# Receiver.net
KiCad netlist of a schematic drawn in EAGLE
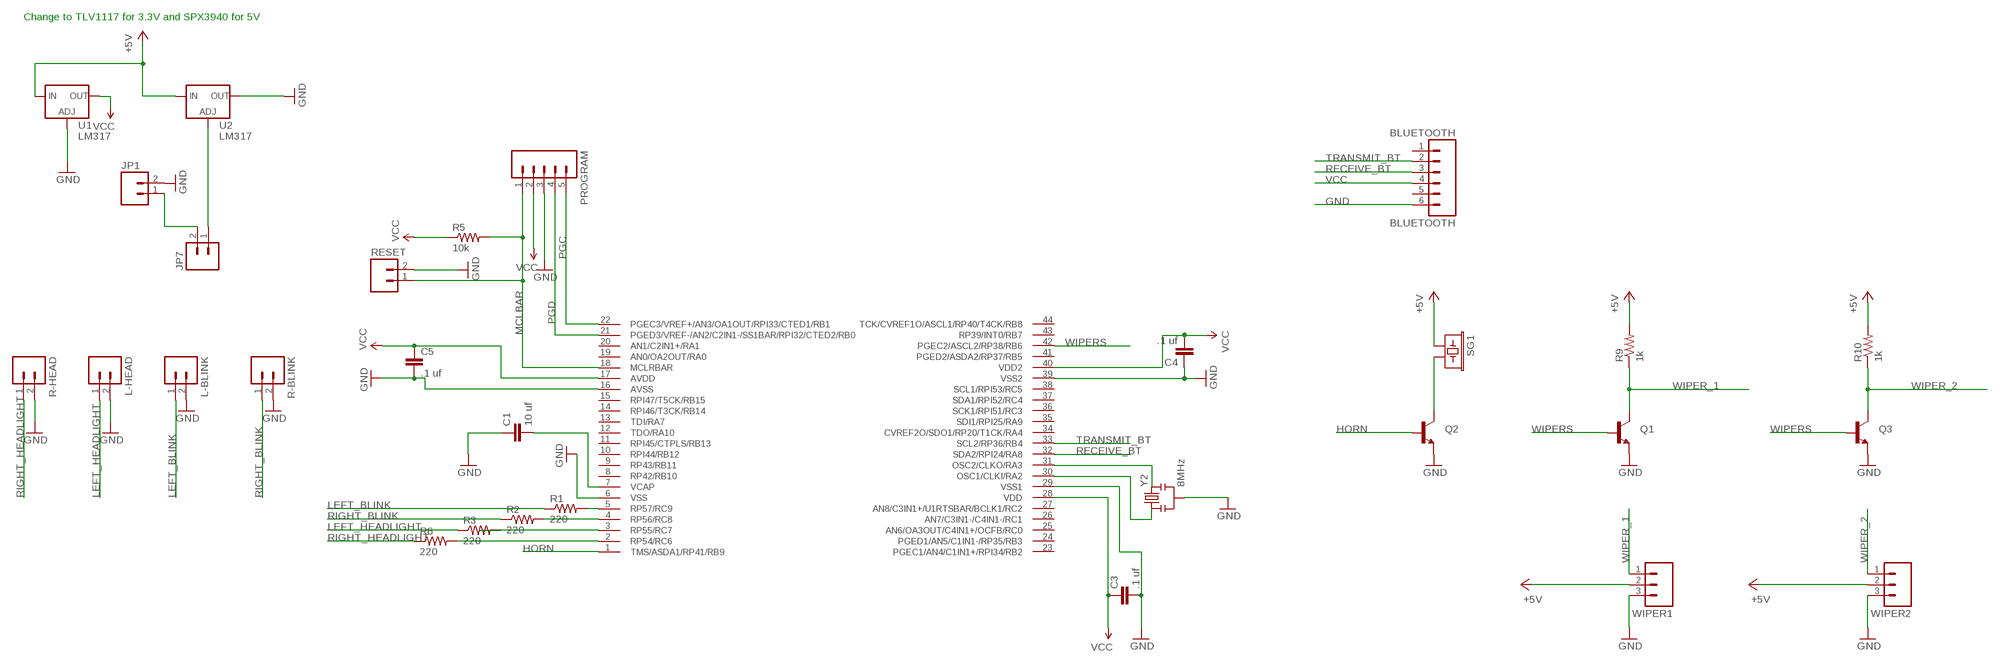
[diagram p0: schematic, sheet 1]

(export (version "E")
  (design (tool "Eeschema 10.0.6"))
  (components
    (comp (ref "BLUETOOTH")
      (value "BLUETOOTH")
      (footprint "eagle-import:MOLEX-1X6")
      (libsource (lib "eagle-import") (part "M06POLAR"))
    )
    (comp (ref "C1")
      (value "10 uf")
      (footprint "eagle-import:0603-CAP")
      (libsource (lib "eagle-import") (part "CAP0603-CAP"))
    )
    (comp (ref "C3")
      (value ".1 uf")
      (footprint "eagle-import:0603-CAP")
      (libsource (lib "eagle-import") (part "CAP0603-CAP"))
    )
    (comp (ref "C4")
      (value ".1 uf")
      (footprint "eagle-import:0603-CAP")
      (libsource (lib "eagle-import") (part "CAP0603-CAP"))
    )
    (comp (ref "C5")
      (value ".1 uf")
      (footprint "eagle-import:0603-CAP")
      (libsource (lib "eagle-import") (part "CAP0603-CAP"))
    )
    (comp (ref "JP1")
      (value "M02LOCK")
      (footprint "eagle-import:1X02_LOCK")
      (libsource (lib "eagle-import") (part "M02LOCK"))
    )
    (comp (ref "JP7")
      (value "M02LOCK")
      (footprint "eagle-import:1X02_LOCK")
      (libsource (lib "eagle-import") (part "M02LOCK"))
    )
    (comp (ref "L-BLINK")
      (value "M02LOCK")
      (footprint "eagle-import:1X02_LOCK")
      (libsource (lib "eagle-import") (part "M02LOCK"))
    )
    (comp (ref "L-HEAD")
      (value "M02LOCK")
      (footprint "eagle-import:1X02_LOCK")
      (libsource (lib "eagle-import") (part "M02LOCK"))
    )
    (comp (ref "PROGRAM")
      (value "M05LOCK")
      (footprint "eagle-import:1X05_LOCK")
      (libsource (lib "eagle-import") (part "M05LOCK"))
    )
    (comp (ref "Q1")
      (value "TRANSISTOR_NPNSOT23-3")
      (footprint "eagle-import:SOT23-3")
      (libsource (lib "eagle-import") (part "TRANSISTOR_NPNSOT23-3"))
    )
    (comp (ref "Q2")
      (value "TRANSISTOR_NPNSOT23-3")
      (footprint "eagle-import:SOT23-3")
      (libsource (lib "eagle-import") (part "TRANSISTOR_NPNSOT23-3"))
    )
    (comp (ref "Q3")
      (value "TRANSISTOR_NPNSOT23-3")
      (footprint "eagle-import:SOT23-3")
      (libsource (lib "eagle-import") (part "TRANSISTOR_NPNSOT23-3"))
    )
    (comp (ref "R-BLINK")
      (value "M02LOCK")
      (footprint "eagle-import:1X02_LOCK")
      (libsource (lib "eagle-import") (part "M02LOCK"))
    )
    (comp (ref "R-HEAD")
      (value "M02LOCK")
      (footprint "eagle-import:1X02_LOCK")
      (libsource (lib "eagle-import") (part "M02LOCK"))
    )
    (comp (ref "R1")
      (value "220")
      (footprint "eagle-import:0603-RES")
      (libsource (lib "eagle-import") (part "RESISTOR0603-RES"))
    )
    (comp (ref "R2")
      (value "220")
      (footprint "eagle-import:0603-RES")
      (libsource (lib "eagle-import") (part "RESISTOR0603-RES"))
    )
    (comp (ref "R3")
      (value "220")
      (footprint "eagle-import:0603-RES")
      (libsource (lib "eagle-import") (part "RESISTOR0603-RES"))
    )
    (comp (ref "R5")
      (value "10k")
      (footprint "eagle-import:0603-RES")
      (libsource (lib "eagle-import") (part "RESISTOR0603-RES"))
    )
    (comp (ref "R6")
      (value "220")
      (footprint "eagle-import:0603-RES")
      (libsource (lib "eagle-import") (part "RESISTOR0603-RES"))
    )
    (comp (ref "R9")
      (value "1k")
      (footprint "eagle-import:0603-RES")
      (libsource (lib "eagle-import") (part "RESISTOR0603-RES"))
    )
    (comp (ref "R10")
      (value "1k")
      (footprint "eagle-import:0603-RES")
      (libsource (lib "eagle-import") (part "RESISTOR0603-RES"))
    )
    (comp (ref "RESET")
      (value "M02PTH")
      (footprint "eagle-import:1X02")
      (libsource (lib "eagle-import") (part "M02PTH"))
    )
    (comp (ref "SG1")
      (value "BUZZERNS")
      (footprint "eagle-import:BUZZER-12MM-NS")
      (libsource (lib "eagle-import") (part "BUZZERNS"))
    )
    (comp (ref "U$1")
      (value "TQFP44PIC24EP256GP204")
      (footprint "eagle-import:TQFP44")
      (libsource (lib "eagle-import") (part "TQFP44PIC24EP256GP204"))
    )
    (comp (ref "U1")
      (value "LM317")
      (footprint "eagle-import:SOT223")
      (libsource (lib "eagle-import") (part "V_REG_317SMD"))
    )
    (comp (ref "U2")
      (value "LM317")
      (footprint "eagle-import:SOT223")
      (libsource (lib "eagle-import") (part "V_REG_317SMD"))
    )
    (comp (ref "WIPER1")
      (value "M03LOCK")
      (footprint "eagle-import:1X03_LOCK")
      (libsource (lib "eagle-import") (part "M03LOCK"))
    )
    (comp (ref "WIPER2")
      (value "M03LOCK")
      (footprint "eagle-import:1X03_LOCK")
      (libsource (lib "eagle-import") (part "M03LOCK"))
    )
    (comp (ref "Y2")
      (value "8MHz")
      (footprint "eagle-import:RESONATOR-SMD")
      (libsource (lib "eagle-import") (part "RESONATORSMD"))
    )
  )
  (nets
    (net (code "1") (name "+5V") (class "Default")
      (node (ref "R10") (pin "2") (pinfunction "2_2") (pintype "passive"))
      (node (ref "R9") (pin "2") (pinfunction "2_2") (pintype "passive"))
      (node (ref "SG1") (pin "+") (pinfunction "1_+") (pintype "passive"))
      (node (ref "U1") (pin "3") (pinfunction "IN_3") (pintype "input"))
      (node (ref "U2") (pin "3") (pinfunction "IN_3") (pintype "input"))
      (node (ref "WIPER1") (pin "2") (pinfunction "2_2") (pintype "passive"))
      (node (ref "WIPER2") (pin "2") (pinfunction "2_2") (pintype "passive"))
    )
    (net (code "2") (name "/HORN") (class "Default")
      (node (ref "Q2") (pin "1") (pinfunction "B_1") (pintype "passive"))
      (node (ref "U$1") (pin "1") (pinfunction "TMS/ASDA1/RP41/RB9_1") (pintype "bidirectional"))
    )
    (net (code "3") (name "/LEFT_BLINK") (class "Default")
      (node (ref "L-BLINK") (pin "1") (pinfunction "1_1") (pintype "passive"))
      (node (ref "R1") (pin "1") (pinfunction "1_1") (pintype "passive"))
    )
    (net (code "4") (name "/LEFT_HEADLIGHT") (class "Default")
      (node (ref "L-HEAD") (pin "1") (pinfunction "1_1") (pintype "passive"))
      (node (ref "R3") (pin "1") (pinfunction "1_1") (pintype "passive"))
    )
    (net (code "5") (name "/MCLBAR") (class "Default")
      (node (ref "PROGRAM") (pin "1") (pinfunction "1_1") (pintype "passive"))
      (node (ref "R5") (pin "2") (pinfunction "2_2") (pintype "passive"))
      (node (ref "RESET") (pin "1") (pinfunction "1_1") (pintype "passive"))
      (node (ref "U$1") (pin "18") (pinfunction "MCLRBAR_18") (pintype "bidirectional"))
    )
    (net (code "6") (name "/PGC") (class "Default")
      (node (ref "PROGRAM") (pin "5") (pinfunction "5_5") (pintype "passive"))
      (node (ref "U$1") (pin "22") (pinfunction "PGEC3/VREF+/AN3/OA1OUT/RPI33/CTED1/RB1_22") (pintype "bidirectional"))
    )
    (net (code "7") (name "/PGD") (class "Default")
      (node (ref "PROGRAM") (pin "4") (pinfunction "4_4") (pintype "passive"))
      (node (ref "U$1") (pin "21") (pinfunction "PGED3/VREF-/AN2/C2IN1-/SS1BAR/RPI32/CTED2/RB0_21") (pintype "bidirectional"))
    )
    (net (code "8") (name "/RECEIVE_BT") (class "Default")
      (node (ref "BLUETOOTH") (pin "3") (pinfunction "3_3") (pintype "passive"))
      (node (ref "U$1") (pin "32") (pinfunction "SDA2/RPI24/RA8_32") (pintype "bidirectional"))
    )
    (net (code "9") (name "/RIGHT_BLINK") (class "Default")
      (node (ref "R-BLINK") (pin "1") (pinfunction "1_1") (pintype "passive"))
      (node (ref "R2") (pin "1") (pinfunction "1_1") (pintype "passive"))
    )
    (net (code "10") (name "/RIGHT_HEADLIGHT") (class "Default")
      (node (ref "R-HEAD") (pin "1") (pinfunction "1_1") (pintype "passive"))
      (node (ref "R6") (pin "1") (pinfunction "1_1") (pintype "passive"))
    )
    (net (code "11") (name "/TRANSMIT_BT") (class "Default")
      (node (ref "BLUETOOTH") (pin "2") (pinfunction "2_2") (pintype "passive"))
      (node (ref "U$1") (pin "33") (pinfunction "SCL2/RP36/RB4_33") (pintype "bidirectional"))
    )
    (net (code "12") (name "/WIPERS") (class "Default")
      (node (ref "Q1") (pin "1") (pinfunction "B_1") (pintype "passive"))
      (node (ref "Q3") (pin "1") (pinfunction "B_1") (pintype "passive"))
      (node (ref "U$1") (pin "42") (pinfunction "PGEC2/ASCL2/RP38/RB6_42") (pintype "bidirectional"))
    )
    (net (code "13") (name "/WIPER_1") (class "Default")
      (node (ref "Q1") (pin "3") (pinfunction "C_3") (pintype "passive"))
      (node (ref "R9") (pin "1") (pinfunction "1_1") (pintype "passive"))
      (node (ref "WIPER1") (pin "1") (pinfunction "1_1") (pintype "passive"))
    )
    (net (code "14") (name "/WIPER_2") (class "Default")
      (node (ref "Q3") (pin "3") (pinfunction "C_3") (pintype "passive"))
      (node (ref "R10") (pin "1") (pinfunction "1_1") (pintype "passive"))
      (node (ref "WIPER2") (pin "1") (pinfunction "1_1") (pintype "passive"))
    )
    (net (code "15") (name "GND") (class "Default")
      (node (ref "BLUETOOTH") (pin "6") (pinfunction "6_6") (pintype "passive"))
      (node (ref "C1") (pin "1") (pinfunction "1_1") (pintype "passive"))
      (node (ref "C3") (pin "2") (pinfunction "2_2") (pintype "passive"))
      (node (ref "C4") (pin "1") (pinfunction "1_1") (pintype "passive"))
      (node (ref "C5") (pin "2") (pinfunction "2_2") (pintype "passive"))
      (node (ref "JP1") (pin "2") (pinfunction "2_2") (pintype "passive"))
      (node (ref "L-BLINK") (pin "2") (pinfunction "2_2") (pintype "passive"))
      (node (ref "L-HEAD") (pin "2") (pinfunction "2_2") (pintype "passive"))
      (node (ref "PROGRAM") (pin "3") (pinfunction "3_3") (pintype "passive"))
      (node (ref "Q1") (pin "2") (pinfunction "E_2") (pintype "passive"))
      (node (ref "Q2") (pin "2") (pinfunction "E_2") (pintype "passive"))
      (node (ref "Q3") (pin "2") (pinfunction "E_2") (pintype "passive"))
      (node (ref "R-BLINK") (pin "2") (pinfunction "2_2") (pintype "passive"))
      (node (ref "R-HEAD") (pin "2") (pinfunction "2_2") (pintype "passive"))
      (node (ref "RESET") (pin "2") (pinfunction "2_2") (pintype "passive"))
      (node (ref "U$1") (pin "16") (pinfunction "AVSS_16") (pintype "bidirectional"))
      (node (ref "U$1") (pin "29") (pinfunction "VSS1_29") (pintype "bidirectional"))
      (node (ref "U$1") (pin "39") (pinfunction "VSS2_39") (pintype "bidirectional"))
      (node (ref "U$1") (pin "6") (pinfunction "VSS_6") (pintype "bidirectional"))
      (node (ref "U1") (pin "1") (pinfunction "ADJ_1") (pintype "input"))
      (node (ref "U2") (pin "2") (pinfunction "OUT_2") (pintype "output"))
      (node (ref "WIPER1") (pin "3") (pinfunction "3_3") (pintype "passive"))
      (node (ref "WIPER2") (pin "3") (pinfunction "3_3") (pintype "passive"))
      (node (ref "Y2") (pin "2") (pinfunction "2_2") (pintype "passive"))
    )
    (net (code "16") (name "Net-(JP1-Pad1)") (class "Default")
      (node (ref "JP1") (pin "1") (pinfunction "1_1") (pintype "passive"))
      (node (ref "JP7") (pin "2") (pinfunction "2_2") (pintype "passive"))
    )
    (net (code "17") (name "Net-(Q2-C)") (class "Default")
      (node (ref "Q2") (pin "3") (pinfunction "C_3") (pintype "passive"))
      (node (ref "SG1") (pin "-") (pinfunction "2_-") (pintype "passive"))
    )
    (net (code "18") (name "Net-(U$1-OSC1{slash}CLKI{slash}RA2)") (class "Default")
      (node (ref "U$1") (pin "30") (pinfunction "OSC1/CLKI/RA2_30") (pintype "bidirectional"))
      (node (ref "Y2") (pin "1") (pinfunction "1_1") (pintype "passive"))
    )
    (net (code "19") (name "Net-(U$1-OSC2{slash}CLKO{slash}RA3)") (class "Default")
      (node (ref "U$1") (pin "31") (pinfunction "OSC2/CLKO/RA3_31") (pintype "bidirectional"))
      (node (ref "Y2") (pin "3") (pinfunction "3_3") (pintype "passive"))
    )
    (net (code "20") (name "Net-(U$1-RP54{slash}RC6)") (class "Default")
      (node (ref "R6") (pin "2") (pinfunction "2_2") (pintype "passive"))
      (node (ref "U$1") (pin "2") (pinfunction "RP54/RC6_2") (pintype "bidirectional"))
    )
    (net (code "21") (name "Net-(U$1-RP55{slash}RC7)") (class "Default")
      (node (ref "R3") (pin "2") (pinfunction "2_2") (pintype "passive"))
      (node (ref "U$1") (pin "3") (pinfunction "RP55/RC7_3") (pintype "bidirectional"))
    )
    (net (code "22") (name "Net-(U$1-RP56{slash}RC8)") (class "Default")
      (node (ref "R2") (pin "2") (pinfunction "2_2") (pintype "passive"))
      (node (ref "U$1") (pin "4") (pinfunction "RP56/RC8_4") (pintype "bidirectional"))
    )
    (net (code "23") (name "Net-(U$1-RP57{slash}RC9)") (class "Default")
      (node (ref "R1") (pin "2") (pinfunction "2_2") (pintype "passive"))
      (node (ref "U$1") (pin "5") (pinfunction "RP57/RC9_5") (pintype "bidirectional"))
    )
    (net (code "24") (name "Net-(U$1-VCAP)") (class "Default")
      (node (ref "C1") (pin "2") (pinfunction "2_2") (pintype "passive"))
      (node (ref "U$1") (pin "7") (pinfunction "VCAP_7") (pintype "bidirectional"))
    )
    (net (code "25") (name "Net-(U2-ADJ)") (class "Default")
      (node (ref "JP7") (pin "1") (pinfunction "1_1") (pintype "passive"))
      (node (ref "U2") (pin "1") (pinfunction "ADJ_1") (pintype "input"))
    )
    (net (code "26") (name "VCC") (class "Default")
      (node (ref "BLUETOOTH") (pin "4") (pinfunction "4_4") (pintype "passive"))
      (node (ref "C3") (pin "1") (pinfunction "1_1") (pintype "passive"))
      (node (ref "C4") (pin "2") (pinfunction "2_2") (pintype "passive"))
      (node (ref "C5") (pin "1") (pinfunction "1_1") (pintype "passive"))
      (node (ref "PROGRAM") (pin "2") (pinfunction "2_2") (pintype "passive"))
      (node (ref "R5") (pin "1") (pinfunction "1_1") (pintype "passive"))
      (node (ref "U$1") (pin "17") (pinfunction "AVDD_17") (pintype "bidirectional"))
      (node (ref "U$1") (pin "28") (pinfunction "VDD_28") (pintype "bidirectional"))
      (node (ref "U$1") (pin "40") (pinfunction "VDD2_40") (pintype "bidirectional"))
      (node (ref "U1") (pin "2") (pinfunction "OUT_2") (pintype "output"))
    )
    (net (code "27") (name "unconnected-(BLUETOOTH-Pad1)") (class "Default")
      (node (ref "BLUETOOTH") (pin "1") (pinfunction "1_1") (pintype "passive"))
    )
    (net (code "28") (name "unconnected-(BLUETOOTH-Pad5)") (class "Default")
      (node (ref "BLUETOOTH") (pin "5") (pinfunction "5_5") (pintype "passive"))
    )
    (net (code "29") (name "unconnected-(U$1-AN0{slash}OA2OUT{slash}RA0-Pad19)") (class "Default")
      (node (ref "U$1") (pin "19") (pinfunction "AN0/OA2OUT/RA0_19") (pintype "bidirectional"))
    )
    (net (code "30") (name "unconnected-(U$1-AN1{slash}C2IN1+{slash}RA1-Pad20)") (class "Default")
      (node (ref "U$1") (pin "20") (pinfunction "AN1/C2IN1+/RA1_20") (pintype "bidirectional"))
    )
    (net (code "31") (name "unconnected-(U$1-AN6{slash}OA3OUT{slash}C4IN1+{slash}OCFB{slash}RC0-Pad25)") (class "Default")
      (node (ref "U$1") (pin "25") (pinfunction "AN6/OA3OUT/C4IN1+/OCFB/RC0_25") (pintype "bidirectional"))
    )
    (net (code "32") (name "unconnected-(U$1-AN7{slash}C3IN1-{slash}C4IN1-{slash}RC1-Pad26)") (class "Default")
      (node (ref "U$1") (pin "26") (pinfunction "AN7/C3IN1-/C4IN1-/RC1_26") (pintype "bidirectional"))
    )
    (net (code "33") (name "unconnected-(U$1-AN8{slash}C3IN1+{slash}U1RTSBAR{slash}BCLK1{slash}RC2-Pad27)") (class "Default")
      (node (ref "U$1") (pin "27") (pinfunction "AN8/C3IN1+/U1RTSBAR/BCLK1/RC2_27") (pintype "bidirectional"))
    )
    (net (code "34") (name "unconnected-(U$1-CVREF2O{slash}SDO1{slash}RP20{slash}T1CK{slash}RA4-Pad34)") (class "Default")
      (node (ref "U$1") (pin "34") (pinfunction "CVREF2O/SDO1/RP20/T1CK/RA4_34") (pintype "bidirectional"))
    )
    (net (code "35") (name "unconnected-(U$1-PGEC1{slash}AN4{slash}C1IN1+{slash}RPI34{slash}RB2-Pad23)") (class "Default")
      (node (ref "U$1") (pin "23") (pinfunction "PGEC1/AN4/C1IN1+/RPI34/RB2_23") (pintype "bidirectional"))
    )
    (net (code "36") (name "unconnected-(U$1-PGED1{slash}AN5{slash}C1IN1-{slash}RP35{slash}RB3-Pad24)") (class "Default")
      (node (ref "U$1") (pin "24") (pinfunction "PGED1/AN5/C1IN1-/RP35/RB3_24") (pintype "bidirectional"))
    )
    (net (code "37") (name "unconnected-(U$1-PGED2{slash}ASDA2{slash}RP37{slash}RB5-Pad41)") (class "Default")
      (node (ref "U$1") (pin "41") (pinfunction "PGED2/ASDA2/RP37/RB5_41") (pintype "bidirectional"))
    )
    (net (code "38") (name "unconnected-(U$1-RP39{slash}INT0{slash}RB7-Pad43)") (class "Default")
      (node (ref "U$1") (pin "43") (pinfunction "RP39/INT0/RB7_43") (pintype "bidirectional"))
    )
    (net (code "39") (name "unconnected-(U$1-RP42{slash}RB10-Pad8)") (class "Default")
      (node (ref "U$1") (pin "8") (pinfunction "RP42/RB10_8") (pintype "bidirectional"))
    )
    (net (code "40") (name "unconnected-(U$1-RP43{slash}RB11-Pad9)") (class "Default")
      (node (ref "U$1") (pin "9") (pinfunction "RP43/RB11_9") (pintype "bidirectional"))
    )
    (net (code "41") (name "unconnected-(U$1-RPI44{slash}RB12-Pad10)") (class "Default")
      (node (ref "U$1") (pin "10") (pinfunction "RPI44/RB12_10") (pintype "bidirectional"))
    )
    (net (code "42") (name "unconnected-(U$1-RPI45{slash}CTPLS{slash}RB13-Pad11)") (class "Default")
      (node (ref "U$1") (pin "11") (pinfunction "RPI45/CTPLS/RB13_11") (pintype "bidirectional"))
    )
    (net (code "43") (name "unconnected-(U$1-RPI46{slash}T3CK{slash}RB14-Pad14)") (class "Default")
      (node (ref "U$1") (pin "14") (pinfunction "RPI46/T3CK/RB14_14") (pintype "bidirectional"))
    )
    (net (code "44") (name "unconnected-(U$1-RPI47{slash}T5CK{slash}RB15-Pad15)") (class "Default")
      (node (ref "U$1") (pin "15") (pinfunction "RPI47/T5CK/RB15_15") (pintype "bidirectional"))
    )
    (net (code "45") (name "unconnected-(U$1-SCK1{slash}RPI51{slash}RC3-Pad36)") (class "Default")
      (node (ref "U$1") (pin "36") (pinfunction "SCK1/RPI51/RC3_36") (pintype "bidirectional"))
    )
    (net (code "46") (name "unconnected-(U$1-SCL1{slash}RPI53{slash}RC5-Pad38)") (class "Default")
      (node (ref "U$1") (pin "38") (pinfunction "SCL1/RPI53/RC5_38") (pintype "bidirectional"))
    )
    (net (code "47") (name "unconnected-(U$1-SDA1{slash}RPI52{slash}RC4-Pad37)") (class "Default")
      (node (ref "U$1") (pin "37") (pinfunction "SDA1/RPI52/RC4_37") (pintype "bidirectional"))
    )
    (net (code "48") (name "unconnected-(U$1-SDI1{slash}RPI25{slash}RA9-Pad35)") (class "Default")
      (node (ref "U$1") (pin "35") (pinfunction "SDI1/RPI25/RA9_35") (pintype "bidirectional"))
    )
    (net (code "49") (name "unconnected-(U$1-TCK{slash}CVREF1O{slash}ASCL1{slash}RP40{slash}T4CK{slash}RB8-Pad44)") (class "Default")
      (node (ref "U$1") (pin "44") (pinfunction "TCK/CVREF1O/ASCL1/RP40/T4CK/RB8_44") (pintype "bidirectional"))
    )
    (net (code "50") (name "unconnected-(U$1-TDI{slash}RA7-Pad13)") (class "Default")
      (node (ref "U$1") (pin "13") (pinfunction "TDI/RA7_13") (pintype "bidirectional"))
    )
    (net (code "51") (name "unconnected-(U$1-TDO{slash}RA10-Pad12)") (class "Default")
      (node (ref "U$1") (pin "12") (pinfunction "TDO/RA10_12") (pintype "bidirectional"))
    )
  )
)
